# SL_Power.net
KiCad netlist of a schematic drawn in Altium Designer
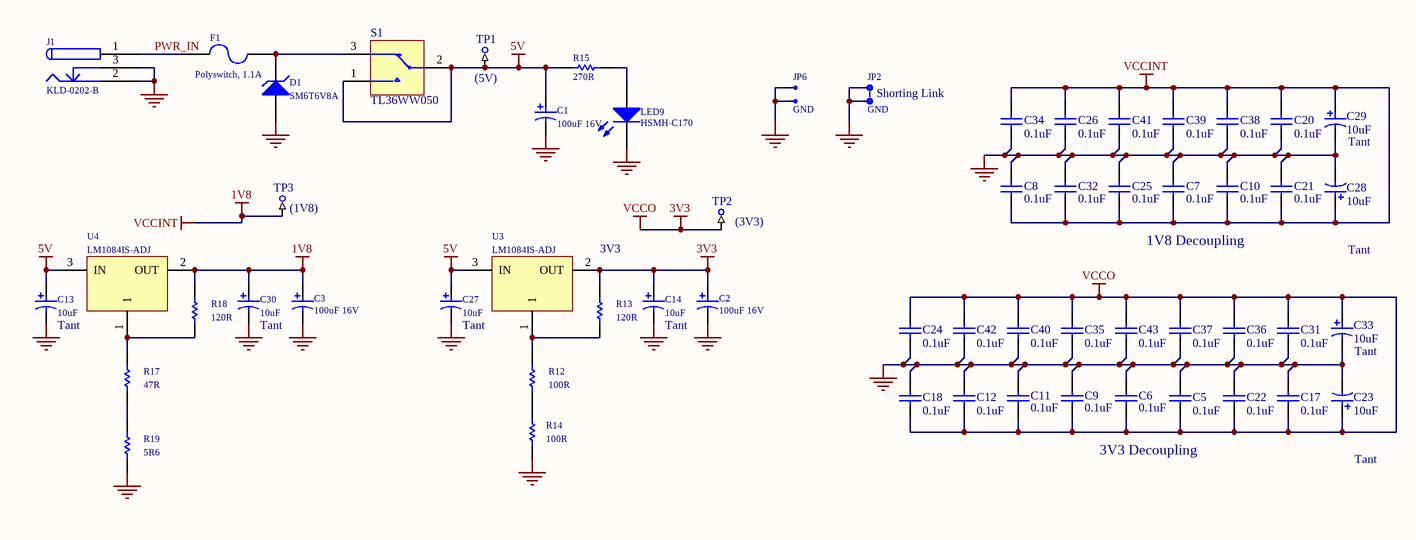
[diagram p0: SL_Power.SchDoc]

(export (version "E")
  (design (tool "Eeschema 10.0.6"))
  (components
    (comp (ref "C1")
      (value "100uF 16V")
      (footprint "CAPPR2-5X6.8")
      (description "Polar Capacitor")
      (libsource (lib "SpiritLevel_2E") (part "CAP_POLAR_1"))
    )
    (comp (ref "C2")
      (value "100uF 16V")
      (footprint "CAPPR2-5X6.8")
      (description "Polar Capacitor")
      (libsource (lib "SpiritLevel_2E") (part "CAP_POLAR_1"))
    )
    (comp (ref "C3")
      (value "100uF 16V")
      (footprint "CAPPR2-5X6.8")
      (description "Polar Capacitor")
      (libsource (lib "SpiritLevel_2E") (part "CAP_POLAR_1"))
    )
    (comp (ref "C5")
      (value "0.1uF")
      (footprint "CC2012-0805")
      (description "Capacitor")
      (libsource (lib "SpiritLevel_2E") (part "CAP"))
    )
    (comp (ref "C6")
      (value "0.1uF")
      (footprint "CC2012-0805")
      (description "Capacitor")
      (libsource (lib "SpiritLevel_2E") (part "CAP"))
    )
    (comp (ref "C7")
      (value "0.1uF")
      (footprint "CC2012-0805")
      (description "Capacitor")
      (libsource (lib "SpiritLevel_2E") (part "CAP"))
    )
    (comp (ref "C8")
      (value "0.1uF")
      (footprint "CC2012-0805")
      (description "Capacitor")
      (libsource (lib "SpiritLevel_2E") (part "CAP"))
    )
    (comp (ref "C9")
      (value "0.1uF")
      (footprint "CC2012-0805")
      (description "Capacitor")
      (libsource (lib "SpiritLevel_2E") (part "CAP"))
    )
    (comp (ref "C10")
      (value "0.1uF")
      (footprint "CC2012-0805")
      (description "Capacitor")
      (libsource (lib "SpiritLevel_2E") (part "CAP"))
    )
    (comp (ref "C11")
      (value "0.1uF")
      (footprint "CC2012-0805")
      (description "Capacitor")
      (libsource (lib "SpiritLevel_2E") (part "CAP"))
    )
    (comp (ref "C12")
      (value "0.1uF")
      (footprint "CC2012-0805")
      (description "Capacitor")
      (libsource (lib "SpiritLevel_2E") (part "CAP"))
    )
    (comp (ref "C13")
      (value "10uF")
      (footprint "Spirit_Level_Project:MCCT-B")
      (description "Polar Capacitor")
      (fields (field (name "CAPACITOR TYPE") "Tant"))
      (libsource (lib "SpiritLevel_2E") (part "CAP_POLAR"))
    )
    (comp (ref "C14")
      (value "10uF")
      (footprint "Spirit_Level_Project:MCCT-B")
      (description "Polar Capacitor")
      (fields (field (name "CAPACITOR TYPE") "Tant"))
      (libsource (lib "SpiritLevel_2E") (part "CAP_POLAR"))
    )
    (comp (ref "C17")
      (value "0.1uF")
      (footprint "CC2012-0805")
      (description "Capacitor")
      (libsource (lib "SpiritLevel_2E") (part "CAP"))
    )
    (comp (ref "C18")
      (value "0.1uF")
      (footprint "CC2012-0805")
      (description "Capacitor")
      (libsource (lib "SpiritLevel_2E") (part "CAP"))
    )
    (comp (ref "C20")
      (value "0.1uF")
      (footprint "CC2012-0805")
      (description "Capacitor")
      (libsource (lib "SpiritLevel_2E") (part "CAP"))
    )
    (comp (ref "C21")
      (value "0.1uF")
      (footprint "CC2012-0805")
      (description "Capacitor")
      (libsource (lib "SpiritLevel_2E") (part "CAP"))
    )
    (comp (ref "C22")
      (value "0.1uF")
      (footprint "CC2012-0805")
      (description "Capacitor")
      (libsource (lib "SpiritLevel_2E") (part "CAP"))
    )
    (comp (ref "C23")
      (value "10uF")
      (footprint "Spirit_Level_Project:MCCT-B")
      (description "Polar Capacitor")
      (fields (field (name "CAPACITOR TYPE") "Tant"))
      (libsource (lib "SpiritLevel_2E") (part "CAP_POLAR"))
    )
    (comp (ref "C24")
      (value "0.1uF")
      (footprint "Spirit_Level_Project:CC2012-0805")
      (description "Capacitor")
      (libsource (lib "SpiritLevel_2E") (part "CAP"))
    )
    (comp (ref "C25")
      (value "0.1uF")
      (footprint "CC2012-0805")
      (description "Capacitor")
      (libsource (lib "SpiritLevel_2E") (part "CAP"))
    )
    (comp (ref "C26")
      (value "0.1uF")
      (footprint "CC2012-0805")
      (description "Capacitor")
      (libsource (lib "SpiritLevel_2E") (part "CAP"))
    )
    (comp (ref "C27")
      (value "10uF")
      (footprint "Spirit_Level_Project:MCCT-B")
      (description "Polar Capacitor")
      (fields (field (name "CAPACITOR TYPE") "Tant"))
      (libsource (lib "SpiritLevel_2E") (part "CAP_POLAR"))
    )
    (comp (ref "C28")
      (value "10uF")
      (footprint "Spirit_Level_Project:MCCT-B")
      (description "Polar Capacitor")
      (fields (field (name "CAPACITOR TYPE") "Tant"))
      (libsource (lib "SpiritLevel_2E") (part "CAP_POLAR"))
    )
    (comp (ref "C29")
      (value "10uF")
      (footprint "Spirit_Level_Project:MCCT-B")
      (description "Polar Capacitor")
      (fields (field (name "CAPACITOR TYPE") "Tant"))
      (libsource (lib "SpiritLevel_2E") (part "CAP_POLAR"))
    )
    (comp (ref "C30")
      (value "10uF")
      (footprint "Spirit_Level_Project:MCCT-B")
      (description "Polar Capacitor")
      (fields (field (name "CAPACITOR TYPE") "Tant"))
      (libsource (lib "SpiritLevel_2E") (part "CAP_POLAR"))
    )
    (comp (ref "C31")
      (value "0.1uF")
      (footprint "CC2012-0805")
      (description "Capacitor")
      (libsource (lib "SpiritLevel_2E") (part "CAP"))
    )
    (comp (ref "C32")
      (value "0.1uF")
      (footprint "CC2012-0805")
      (description "Capacitor")
      (libsource (lib "SpiritLevel_2E") (part "CAP"))
    )
    (comp (ref "C33")
      (value "10uF")
      (footprint "Spirit_Level_Project:MCCT-B")
      (description "Polar Capacitor")
      (fields (field (name "CAPACITOR TYPE") "Tant"))
      (libsource (lib "SpiritLevel_2E") (part "CAP_POLAR"))
    )
    (comp (ref "C34")
      (value "0.1uF")
      (footprint "CC2012-0805")
      (description "Capacitor")
      (libsource (lib "SpiritLevel_2E") (part "CAP"))
    )
    (comp (ref "C35")
      (value "0.1uF")
      (footprint "CC2012-0805")
      (description "Capacitor")
      (libsource (lib "SpiritLevel_2E") (part "CAP"))
    )
    (comp (ref "C36")
      (value "0.1uF")
      (footprint "CC2012-0805")
      (description "Capacitor")
      (libsource (lib "SpiritLevel_2E") (part "CAP"))
    )
    (comp (ref "C37")
      (value "0.1uF")
      (footprint "CC2012-0805")
      (description "Capacitor")
      (libsource (lib "SpiritLevel_2E") (part "CAP"))
    )
    (comp (ref "C38")
      (value "0.1uF")
      (footprint "CC2012-0805")
      (description "Capacitor")
      (libsource (lib "SpiritLevel_2E") (part "CAP"))
    )
    (comp (ref "C39")
      (value "0.1uF")
      (footprint "CC2012-0805")
      (description "Capacitor")
      (libsource (lib "SpiritLevel_2E") (part "CAP"))
    )
    (comp (ref "C40")
      (value "0.1uF")
      (footprint "CC2012-0805")
      (description "Capacitor")
      (libsource (lib "SpiritLevel_2E") (part "CAP"))
    )
    (comp (ref "C41")
      (value "0.1uF")
      (footprint "CC2012-0805")
      (description "Capacitor")
      (libsource (lib "SpiritLevel_2E") (part "CAP"))
    )
    (comp (ref "C42")
      (value "0.1uF")
      (footprint "CC2012-0805")
      (description "Capacitor")
      (libsource (lib "SpiritLevel_2E") (part "CAP"))
    )
    (comp (ref "C43")
      (value "0.1uF")
      (footprint "CC2012-0805")
      (description "Capacitor")
      (libsource (lib "SpiritLevel_2E") (part "CAP"))
    )
    (comp (ref "D1")
      (value "SM6T6V8A")
      (footprint "Spirit_Level_Project:DO214")
      (description "Zener Diode, 6.2V, 5W")
      (fields (field (name "MANUFACTURER") "Microsemi"))
      (libsource (lib "SpiritLevel_2E") (part "BZG03C13"))
    )
    (comp (ref "F1")
      (value "Polyswitch, 1.1A")
      (footprint "Spirit_Level_Project:RUE160_0.2")
      (description "Polyswitch 1.1A, Raychem RUE110")
      (libsource (lib "SpiritLevel_2E") (part "Fuse 2"))
    )
    (comp (ref "J1")
      (value "KLD-0202-B")
      (footprint "Spirit_Level_Project:KLD-0202")
      (description "Low Voltage Power Supply Connector")
      (fields (field (name "MANUFACTURER") "Kycon"))
      (libsource (lib "SpiritLevel_2E") (part "KLD-0202-B"))
    )
    (comp (ref "JP2")
      (value "GND")
      (footprint "Spirit_Level_Project:HDR1X2")
      (description "Jumper, 2-Pin")
      (libsource (lib "SpiritLevel_2E") (part "Jumper, 2-Pin"))
    )
    (comp (ref "JP6")
      (value "GND")
      (footprint "Spirit_Level_Project:HDR1X2")
      (description "Jumper, 2-Pin")
      (libsource (lib "SpiritLevel_2E") (part "Jumper, 2-Pin"))
    )
    (comp (ref "JS1")
      (value "Shorting Link")
      (description "Shorting Link, 2.54mm (0.1\") Pitch")
      (libsource (lib "SpiritLevel_2E") (part "Jumper Socket"))
    )
    (comp (ref "LED9")
      (value "HSMH-C170")
      (footprint "Spirit_Level_Project:SMD _LED")
      (description "Typical RED GaAs SMD LED Agilent make")
      (libsource (lib "SpiritLevel_2E") (part "HSMX-C670"))
    )
    (comp (ref "R12")
      (value "100R")
      (footprint "CC2012-0805")
      (description "Resistor")
      (libsource (lib "SpiritLevel_2E") (part "RES"))
    )
    (comp (ref "R13")
      (value "120R")
      (footprint "CC2012-0805")
      (description "Resistor")
      (libsource (lib "SpiritLevel_2E") (part "RES"))
    )
    (comp (ref "R14")
      (value "100R")
      (footprint "CC2012-0805")
      (description "Resistor")
      (libsource (lib "SpiritLevel_2E") (part "RES"))
    )
    (comp (ref "R15")
      (value "270R")
      (footprint "Spirit_Level_Project:CR2012-0805")
      (description "Resistor")
      (libsource (lib "SpiritLevel_2E") (part "RES"))
    )
    (comp (ref "R17")
      (value "47R")
      (footprint "CC2012-0805")
      (description "Resistor")
      (libsource (lib "SpiritLevel_2E") (part "RES"))
    )
    (comp (ref "R18")
      (value "120R")
      (footprint "CC2012-0805")
      (description "Resistor")
      (libsource (lib "SpiritLevel_2E") (part "RES"))
    )
    (comp (ref "R19")
      (value "5R6")
      (footprint "CC2012-0805")
      (description "Resistor")
      (libsource (lib "SpiritLevel_2E") (part "RES"))
    )
    (comp (ref "S1")
      (value "TL36WW050")
      (footprint "Spirit_Level_Project:PCB_SWITCH")
      (description "SPDT Subminiature Toggle Switch")
      (libsource (lib "SpiritLevel_2E") (part "PCB_MOUNT_SWITCH"))
    )
    (comp (ref "TP1")
      (value "(5V)")
      (footprint "Spirit_Level_Project:TP")
      (libsource (lib "SpiritLevel_2E") (part "TestPin"))
    )
    (comp (ref "TP2")
      (value "(3V3)")
      (footprint "Spirit_Level_Project:TP")
      (libsource (lib "SpiritLevel_2E") (part "TestPin"))
    )
    (comp (ref "TP3")
      (value "(1V8)")
      (footprint "Spirit_Level_Project:TP")
      (libsource (lib "SpiritLevel_2E") (part "TestPin"))
    )
    (comp (ref "U3")
      (value "LM1084IS-ADJ")
      (footprint "Spirit_Level_Project:TO-263")
      (description "5A Low Dropout Possitive Regulators")
      (libsource (lib "SpiritLevel_2E") (part "LM1084IS-ADJ"))
    )
    (comp (ref "U4")
      (value "LM1084IS-ADJ")
      (footprint "Spirit_Level_Project:TO-263")
      (description "5A Low Dropout Possitive Regulators")
      (libsource (lib "SpiritLevel_2E") (part "LM1084IS-ADJ"))
    )
  )
  (nets
    (net (code "1") (name "/PWR_IN") (class "Default")
      (node (ref "F1") (pin "1") (pinfunction "1_1") (pintype "passive"))
      (node (ref "J1") (pin "1") (pintype "power_in"))
    )
    (net (code "2") (name "1V8") (class "Default")
      (node (ref "C10") (pin "1") (pinfunction "1_1") (pintype "passive"))
      (node (ref "C20") (pin "1") (pinfunction "1_1") (pintype "passive"))
      (node (ref "C21") (pin "1") (pinfunction "1_1") (pintype "passive"))
      (node (ref "C25") (pin "1") (pinfunction "1_1") (pintype "passive"))
      (node (ref "C26") (pin "1") (pinfunction "1_1") (pintype "passive"))
      (node (ref "C28") (pin "1") (pinfunction "1_1") (pintype "passive"))
      (node (ref "C29") (pin "1") (pinfunction "1_1") (pintype "passive"))
      (node (ref "C3") (pin "1") (pinfunction "1_1") (pintype "passive"))
      (node (ref "C30") (pin "1") (pinfunction "1_1") (pintype "passive"))
      (node (ref "C32") (pin "1") (pinfunction "1_1") (pintype "passive"))
      (node (ref "C34") (pin "2") (pinfunction "2_2") (pintype "passive"))
      (node (ref "C38") (pin "1") (pinfunction "1_1") (pintype "passive"))
      (node (ref "C39") (pin "1") (pinfunction "1_1") (pintype "passive"))
      (node (ref "C41") (pin "1") (pinfunction "1_1") (pintype "passive"))
      (node (ref "C7") (pin "1") (pinfunction "1_1") (pintype "passive"))
      (node (ref "C8") (pin "1") (pinfunction "1_1") (pintype "passive"))
      (node (ref "R18") (pin "1") (pinfunction "1_1") (pintype "passive"))
      (node (ref "TP3") (pin "1") (pinfunction "1_1") (pintype "input"))
      (node (ref "U4") (pin "2") (pinfunction "OUT_2") (pintype "power_in"))
    )
    (net (code "3") (name "3V3") (class "Default")
      (node (ref "C11") (pin "1") (pinfunction "1_1") (pintype "passive"))
      (node (ref "C12") (pin "1") (pinfunction "1_1") (pintype "passive"))
      (node (ref "C14") (pin "1") (pinfunction "1_1") (pintype "passive"))
      (node (ref "C17") (pin "2") (pinfunction "2_2") (pintype "passive"))
      (node (ref "C18") (pin "2") (pinfunction "2_2") (pintype "passive"))
      (node (ref "C2") (pin "1") (pinfunction "1_1") (pintype "passive"))
      (node (ref "C22") (pin "2") (pinfunction "2_2") (pintype "passive"))
      (node (ref "C23") (pin "1") (pinfunction "1_1") (pintype "passive"))
      (node (ref "C24") (pin "2") (pinfunction "2_2") (pintype "passive"))
      (node (ref "C31") (pin "1") (pinfunction "1_1") (pintype "passive"))
      (node (ref "C33") (pin "1") (pinfunction "1_1") (pintype "passive"))
      (node (ref "C35") (pin "1") (pinfunction "1_1") (pintype "passive"))
      (node (ref "C36") (pin "2") (pinfunction "2_2") (pintype "passive"))
      (node (ref "C37") (pin "1") (pinfunction "1_1") (pintype "passive"))
      (node (ref "C40") (pin "1") (pinfunction "1_1") (pintype "passive"))
      (node (ref "C42") (pin "1") (pinfunction "1_1") (pintype "passive"))
      (node (ref "C43") (pin "1") (pinfunction "1_1") (pintype "passive"))
      (node (ref "C5") (pin "2") (pinfunction "2_2") (pintype "passive"))
      (node (ref "C6") (pin "1") (pinfunction "1_1") (pintype "passive"))
      (node (ref "C9") (pin "1") (pinfunction "1_1") (pintype "passive"))
      (node (ref "R13") (pin "1") (pinfunction "1_1") (pintype "passive"))
      (node (ref "TP2") (pin "1") (pinfunction "1_1") (pintype "input"))
      (node (ref "U3") (pin "2") (pinfunction "OUT_2") (pintype "power_in"))
    )
    (net (code "4") (name "5V") (class "Default")
      (node (ref "C1") (pin "1") (pinfunction "1_1") (pintype "passive"))
      (node (ref "C13") (pin "1") (pinfunction "1_1") (pintype "passive"))
      (node (ref "C27") (pin "1") (pinfunction "1_1") (pintype "passive"))
      (node (ref "R15") (pin "2") (pinfunction "2_2") (pintype "passive"))
      (node (ref "S1") (pin "1") (pintype "passive"))
      (node (ref "S1") (pin "2") (pintype "passive"))
      (node (ref "TP1") (pin "1") (pinfunction "1_1") (pintype "input"))
      (node (ref "U3") (pin "3") (pinfunction "IN_3") (pintype "power_in"))
      (node (ref "U4") (pin "3") (pinfunction "IN_3") (pintype "power_in"))
    )
    (net (code "5") (name "GND") (class "Default")
      (node (ref "C1") (pin "2") (pinfunction "2_2") (pintype "passive"))
      (node (ref "C10") (pin "2") (pinfunction "2_2") (pintype "passive"))
      (node (ref "C11") (pin "2") (pinfunction "2_2") (pintype "passive"))
      (node (ref "C12") (pin "2") (pinfunction "2_2") (pintype "passive"))
      (node (ref "C13") (pin "2") (pinfunction "2_2") (pintype "passive"))
      (node (ref "C14") (pin "2") (pinfunction "2_2") (pintype "passive"))
      (node (ref "C17") (pin "1") (pinfunction "1_1") (pintype "passive"))
      (node (ref "C18") (pin "1") (pinfunction "1_1") (pintype "passive"))
      (node (ref "C2") (pin "2") (pinfunction "2_2") (pintype "passive"))
      (node (ref "C20") (pin "2") (pinfunction "2_2") (pintype "passive"))
      (node (ref "C21") (pin "2") (pinfunction "2_2") (pintype "passive"))
      (node (ref "C22") (pin "1") (pinfunction "1_1") (pintype "passive"))
      (node (ref "C23") (pin "2") (pinfunction "2_2") (pintype "passive"))
      (node (ref "C24") (pin "1") (pinfunction "1_1") (pintype "passive"))
      (node (ref "C25") (pin "2") (pinfunction "2_2") (pintype "passive"))
      (node (ref "C26") (pin "2") (pinfunction "2_2") (pintype "passive"))
      (node (ref "C27") (pin "2") (pinfunction "2_2") (pintype "passive"))
      (node (ref "C28") (pin "2") (pinfunction "2_2") (pintype "passive"))
      (node (ref "C29") (pin "2") (pinfunction "2_2") (pintype "passive"))
      (node (ref "C3") (pin "2") (pinfunction "2_2") (pintype "passive"))
      (node (ref "C30") (pin "2") (pinfunction "2_2") (pintype "passive"))
      (node (ref "C31") (pin "2") (pinfunction "2_2") (pintype "passive"))
      (node (ref "C32") (pin "2") (pinfunction "2_2") (pintype "passive"))
      (node (ref "C33") (pin "2") (pinfunction "2_2") (pintype "passive"))
      (node (ref "C34") (pin "1") (pinfunction "1_1") (pintype "passive"))
      (node (ref "C35") (pin "2") (pinfunction "2_2") (pintype "passive"))
      (node (ref "C36") (pin "1") (pinfunction "1_1") (pintype "passive"))
      (node (ref "C37") (pin "2") (pinfunction "2_2") (pintype "passive"))
      (node (ref "C38") (pin "2") (pinfunction "2_2") (pintype "passive"))
      (node (ref "C39") (pin "2") (pinfunction "2_2") (pintype "passive"))
      (node (ref "C40") (pin "2") (pinfunction "2_2") (pintype "passive"))
      (node (ref "C41") (pin "2") (pinfunction "2_2") (pintype "passive"))
      (node (ref "C42") (pin "2") (pinfunction "2_2") (pintype "passive"))
      (node (ref "C43") (pin "2") (pinfunction "2_2") (pintype "passive"))
      (node (ref "C5") (pin "1") (pinfunction "1_1") (pintype "passive"))
      (node (ref "C6") (pin "2") (pinfunction "2_2") (pintype "passive"))
      (node (ref "C7") (pin "2") (pinfunction "2_2") (pintype "passive"))
      (node (ref "C8") (pin "2") (pinfunction "2_2") (pintype "passive"))
      (node (ref "C9") (pin "2") (pinfunction "2_2") (pintype "passive"))
      (node (ref "D1") (pin "1") (pinfunction "A_1") (pintype "passive"))
      (node (ref "J1") (pin "2") (pintype "power_in"))
      (node (ref "J1") (pin "3") (pintype "power_in"))
      (node (ref "JP2") (pin "1") (pinfunction "1_1") (pintype "passive"))
      (node (ref "JP2") (pin "2") (pinfunction "2_2") (pintype "passive"))
      (node (ref "JP6") (pin "1") (pinfunction "1_1") (pintype "passive"))
      (node (ref "JP6") (pin "2") (pinfunction "2_2") (pintype "passive"))
      (node (ref "LED9") (pin "2") (pinfunction "K_2") (pintype "passive"))
      (node (ref "R14") (pin "1") (pinfunction "1_1") (pintype "passive"))
      (node (ref "R19") (pin "2") (pinfunction "2_2") (pintype "passive"))
    )
    (net (code "6") (name "Net-(D1-K)") (class "Default")
      (node (ref "D1") (pin "2") (pinfunction "K_2") (pintype "passive"))
      (node (ref "F1") (pin "2") (pinfunction "2_2") (pintype "passive"))
      (node (ref "S1") (pin "3") (pintype "passive"))
    )
    (net (code "7") (name "Net-(LED9-A)") (class "Default")
      (node (ref "LED9") (pin "1") (pinfunction "A_1") (pintype "passive"))
      (node (ref "R15") (pin "1") (pinfunction "1_1") (pintype "passive"))
    )
    (net (code "8") (name "Net-(R12-Pad1)") (class "Default")
      (node (ref "R12") (pin "1") (pinfunction "1_1") (pintype "passive"))
      (node (ref "R13") (pin "2") (pinfunction "2_2") (pintype "passive"))
      (node (ref "U3") (pin "1") (pinfunction "1_1") (pintype "passive"))
    )
    (net (code "9") (name "Net-(R12-Pad2)") (class "Default")
      (node (ref "R12") (pin "2") (pinfunction "2_2") (pintype "passive"))
      (node (ref "R14") (pin "2") (pinfunction "2_2") (pintype "passive"))
    )
    (net (code "10") (name "Net-(R17-Pad1)") (class "Default")
      (node (ref "R17") (pin "1") (pinfunction "1_1") (pintype "passive"))
      (node (ref "R18") (pin "2") (pinfunction "2_2") (pintype "passive"))
      (node (ref "U4") (pin "1") (pinfunction "1_1") (pintype "passive"))
    )
    (net (code "11") (name "Net-(R17-Pad2)") (class "Default")
      (node (ref "R17") (pin "2") (pinfunction "2_2") (pintype "passive"))
      (node (ref "R19") (pin "1") (pinfunction "1_1") (pintype "passive"))
    )
  )
)
